# RMP_MAIN_HFB.net
KiCad netlist of a schematic drawn in Altium Designer
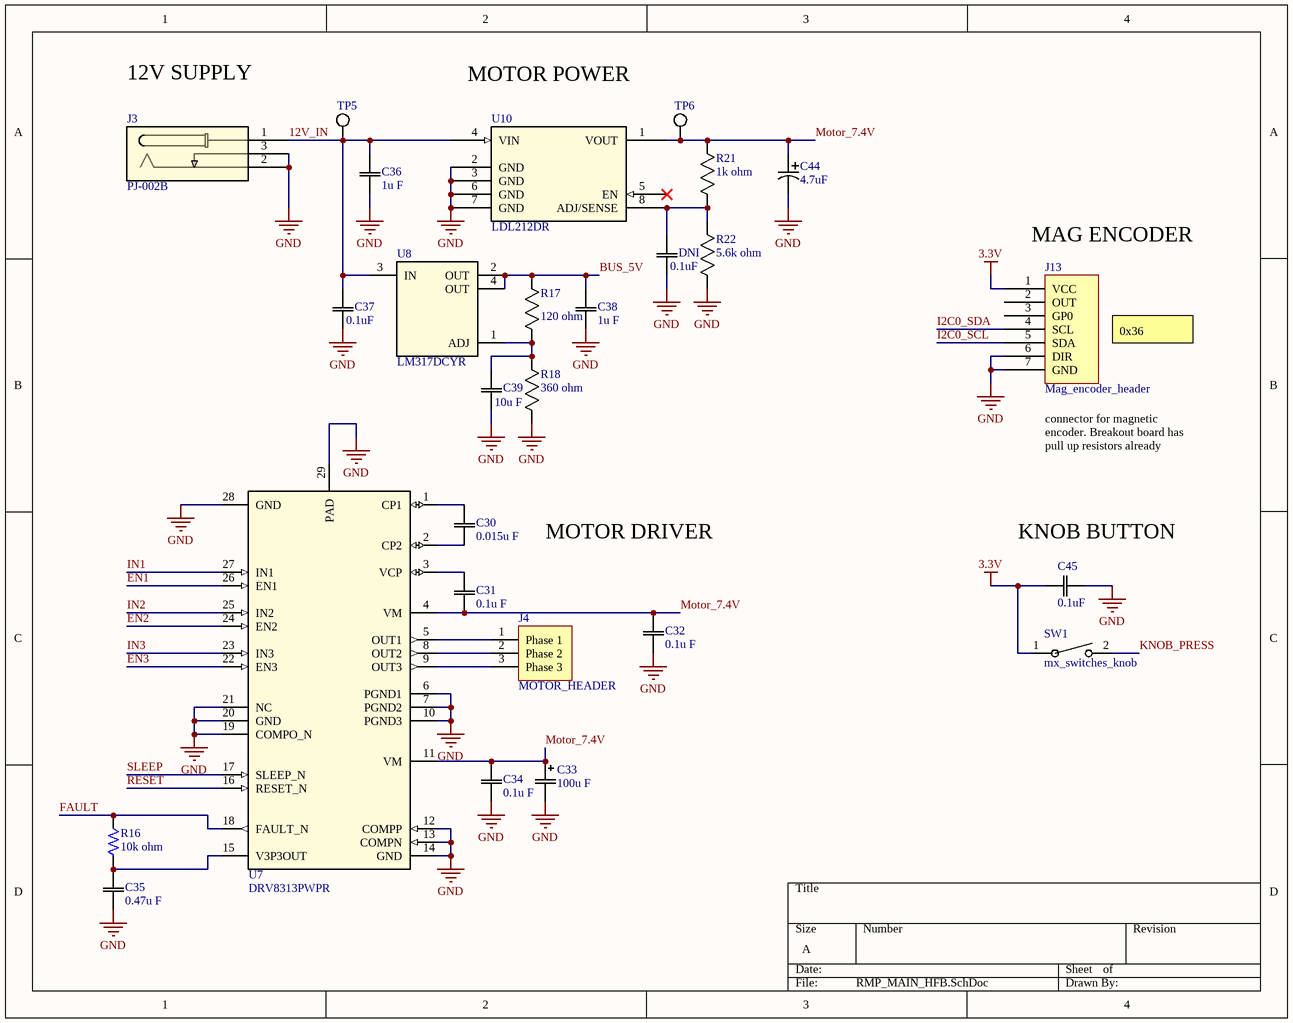
[diagram p0: RMP_MAIN_HFB.SchDoc]

(export (version "E")
  (design (tool "Eeschema 10.0.6"))
  (components
    (comp (ref "C30")
      (value "0.015u F")
      (footprint "CC0805N_YAG-M")
      (description "0.015 µF ±10% 50V Ceramic Capacitor X7R 0805 (2012 Metric)")
      (fields (field (name "Comment") "CC0805KRX7R9BB153"))
      (libsource (lib "Schlib1") (part "CAP_CC0805KRX7R9BB153"))
    )
    (comp (ref "C31")
      (value "0.1u F")
      (footprint "CC0805N_YAG-M")
      (description "0.1 µF ±10% 50V Ceramic Capacitor X7R 0805 (2012 Metric)")
      (fields (field (name "Comment") "CC0805KRX7R9BB104"))
      (libsource (lib "Schlib1") (part "CAP_CC0805KRX7R9BB104"))
    )
    (comp (ref "C32")
      (value "0.1u F")
      (footprint "CC0805N_YAG-M")
      (description "0.1 µF ±10% 50V Ceramic Capacitor X7R 0805 (2012 Metric)")
      (fields (field (name "Comment") "CC0805KRX7R9BB104"))
      (libsource (lib "Schlib1") (part "CAP_CC0805KRX7R9BB104"))
    )
    (comp (ref "C33")
      (value "100u F")
      (footprint "CAP_YX_6P3X11_RUB")
      (description "CAP ALUM 100UF 20% 35V RADIAL TH")
      (fields (field (name "Comment") "35YXJ100M6.3X11"))
      (libsource (lib "Schlib1") (part "CAP_35YXJ100M6.3X11"))
    )
    (comp (ref "C34")
      (value "0.1u F")
      (footprint "CC0805N_YAG-M")
      (description "0.1 µF ±10% 50V Ceramic Capacitor X7R 0805 (2012 Metric)")
      (fields (field (name "Comment") "CC0805KRX7R9BB104"))
      (libsource (lib "Schlib1") (part "CAP_CC0805KRX7R9BB104"))
    )
    (comp (ref "C35")
      (value "0.47u F")
      (footprint "CC0805N_YAG-M")
      (description "0.47 µF ±10% 25V Ceramic Capacitor X7R 0805 (2012 Metric)")
      (fields (field (name "Comment") "CC0805KKX7R8BB474"))
      (libsource (lib "Schlib1") (part "CAP_CC0805KKX7R8BB474"))
    )
    (comp (ref "C36")
      (value "1u F")
      (footprint "CAP_CL21B105KAFNNNE_SAM-M")
      (description "1 µF ±10% 25V Ceramic Capacitor X7R 0805 (2012 Metric)")
      (fields (field (name "Comment") "CL21B105KAFNNNE"))
      (libsource (lib "Schlib1") (part "CAP_CL21B105KAFNNNE"))
    )
    (comp (ref "C37")
      (value "0.1uF")
      (footprint "CC0805N_YAG-M")
      (description "0.1 µF ±10% 50V Ceramic Capacitor X7R 0805 (2012 Metric)")
      (fields (field (name "Comment") "CC0805KRX7R9BB104"))
      (libsource (lib "Schlib1") (part "CAP_CC0805KRX7R9BB104"))
    )
    (comp (ref "C38")
      (value "1u F")
      (footprint "CAP_CL21B105KAFNNNE_SAM-M")
      (description "1 µF ±10% 25V Ceramic Capacitor X7R 0805 (2012 Metric)")
      (fields (field (name "Comment") "CL21B105KAFNNNE"))
      (libsource (lib "Schlib1") (part "CAP_CL21B105KAFNNNE"))
    )
    (comp (ref "C39")
      (value "10u F")
      (footprint "G-21_MUR-M")
      (description "10 µF ±10% 16V Ceramic Capacitor X5R 0805 (2012 Metric)")
      (fields (field (name "Comment") "GRM21BR61C106KE15K"))
      (libsource (lib "Schlib1") (part "CAP_GRM21BR61C106KE15K"))
    )
    (comp (ref "C44")
      (value "4.7uF")
      (footprint "TAJA_AVX-M")
      (description "4.7 µF Molded Tantalum Capacitors 16 V 1206 (3216 Metric) 4Ohm")
      (fields (field (name "Comment") "TAJA475K016RNJ"))
      (libsource (lib "Schlib1") (part "CAP_TAJA475K016RNJ"))
    )
    (comp (ref "C45")
      (value "0.1uF")
      (footprint "CC0805N_YAG-M")
      (description "0.1 µF ±10% 50V Ceramic Capacitor X7R 0805 (2012 Metric)")
      (fields (field (name "Comment") "CC0805KRX7R9BB104"))
      (libsource (lib "Schlib1") (part "CAP_CC0805KRX7R9BB104"))
    )
    (comp (ref "DNI")
      (value "0.1uF")
      (footprint "CC0805N_YAG-M")
      (description "0.1 µF ±10% 50V Ceramic Capacitor X7R 0805 (2012 Metric)")
      (fields (field (name "Comment") "CC0805KRX7R9BB104"))
      (libsource (lib "Schlib1") (part "CAP_CC0805KRX7R9BB104"))
    )
    (comp (ref "J3")
      (value "PJ-002B")
      (footprint "PJ-002B_CUI")
      (description "Power Barrel Connector Jack 2.50mm ID (0.098\"), 5.50mm OD (0.217\") Through Hole, Right Angle")
      (libsource (lib "Schlib1") (part "PJ-002B"))
    )
    (comp (ref "J4")
      (value "MOTOR_HEADER")
      (footprint "3PINHEADER")
      (description "BLDC motor header")
      (libsource (lib "Schlib1") (part "MOTOR_HEADER"))
    )
    (comp (ref "J13")
      (value "Mag_encoder_header")
      (footprint "8PinHeader")
      (libsource (lib "Schlib1") (part "Mag_encoder_header"))
    )
    (comp (ref "R16")
      (value "10k ohm")
      (footprint "STA_RNCP0805_STP-M")
      (description "10 kOhms ±1% 0.25W, 1/4W Chip Resistor 0805 (2012 Metric) Anti-Sulfur Thin Film")
      (fields (field (name "Comment") "RNCP0805FTD10K0"))
      (libsource (lib "Schlib1") (part "RES_RNCP0805FTD10K0"))
    )
    (comp (ref "R17")
      (value "120 ohm")
      (footprint "RES_RNCF0805_STP-M")
      (description "120 Ohms ±0.5% 0.25W, 1/4W Chip Resistor 0805 (2012 Metric) Automotive AEC-Q200 Thin Film")
      (fields (field (name "Comment") "RNCF0805DTE120R"))
      (libsource (lib "Schlib1") (part "RES_RNCF0805DTE120R"))
    )
    (comp (ref "R18")
      (value "360 ohm")
      (footprint "RES_RNCF0805_STP-M")
      (description "360 Ohms ±0.5% 0.25W, 1/4W Chip Resistor 0805 (2012 Metric) Automotive AEC-Q200 Thin Film")
      (fields (field (name "Comment") "RNCF0805DTE360R"))
      (libsource (lib "Schlib1") (part "RES_RNCF0805DTE360R"))
    )
    (comp (ref "R21")
      (value "1k ohm")
      (footprint "RES_RNCF0805_STP-M")
      (description "1 kOhms ±0.5% 0.25W, 1/4W Chip Resistor 0805 (2012 Metric) Automotive AEC-Q200 Thin Film")
      (fields (field (name "Comment") "RNCF0805DTE1K00"))
      (libsource (lib "Schlib1") (part "RES_RNCF0805DTE1K00"))
    )
    (comp (ref "R22")
      (value "5.6k ohm")
      (footprint "RES_RNCF0805_STP-M")
      (description "5.6 kOhms ±0.5% 0.25W, 1/4W Chip Resistor 0805 (2012 Metric) Automotive AEC-Q200 Thin Film")
      (fields (field (name "Comment") "RNCF0805DTE5K60"))
      (libsource (lib "Schlib1") (part "RES_RNCF0805DTE5K60"))
    )
    (comp (ref "SW1")
      (value "mx_switches_knob")
      (footprint "knob_switches")
      (description "No Description Available")
      (libsource (lib "Schlib1") (part "mx_switches_knob"))
    )
    (comp (ref "TP5")
      (value "TestPoint")
      (footprint "Testpoint")
      (libsource (lib "Schlib1") (part "TestPoint"))
    )
    (comp (ref "TP6")
      (value "TestPoint")
      (footprint "Testpoint")
      (libsource (lib "Schlib1") (part "TestPoint"))
    )
    (comp (ref "U7")
      (value "DRV8313PWPR")
      (footprint "PWP0028F_M")
      (description "IC MOTOR DRIVER 8V-60V 28HTSSOP")
      (libsource (lib "Schlib1") (part "DRV8313PWPR"))
    )
    (comp (ref "U8")
      (value "LM317DCYR")
      (footprint "DCY0004A_M")
      (description "Linear Voltage Regulator IC Positive Adjustable 1 Output 1.5A SOT-223-4")
      (fields
        (field (name "ALTERNATE_PARTNUMBER") "LM317DCY")
        (field (name "MANUFACTURER") "Texas Instruments")
        (field (name "SYMBOLCREATER") "Altium")
      )
      (libsource (lib "Schlib1") (part "LM317DCYR"))
    )
    (comp (ref "U10")
      (value "LDL212DR")
      (footprint "SO8B_4X5X1P27_STM")
      (description "Linear Voltage Regulator IC Positive Adjustable 1 Output 1.2A 8-SO")
      (libsource (lib "Schlib1") (part "LDL212DR"))
    )
  )
  (nets
    (net (code "1") (name "/12V_IN") (class "Default")
      (node (ref "C36") (pin "2") (pinfunction "2_2") (pintype "passive"))
      (node (ref "C37") (pin "2") (pinfunction "2_2") (pintype "passive"))
      (node (ref "J3") (pin "1") (pinfunction "1_1") (pintype "passive"))
      (node (ref "TP5") (pin "1") (pinfunction "1_1") (pintype "passive"))
      (node (ref "U10") (pin "4") (pinfunction "VIN_4") (pintype "input"))
      (node (ref "U8") (pin "3") (pinfunction "IN_3") (pintype "power_in"))
    )
    (net (code "2") (name "/BUS_5V") (class "Default")
      (node (ref "C38") (pin "2") (pinfunction "2_2") (pintype "passive"))
      (node (ref "R17") (pin "2") (pinfunction "2_2") (pintype "passive"))
      (node (ref "U8") (pin "2") (pinfunction "OUT_2") (pintype "power_in"))
      (node (ref "U8") (pin "4") (pinfunction "OUT_4") (pintype "power_in"))
    )
    (net (code "3") (name "/EN1") (class "Default")
      (node (ref "U7") (pin "26") (pinfunction "EN1_26") (pintype "input"))
    )
    (net (code "4") (name "/EN2") (class "Default")
      (node (ref "U7") (pin "24") (pinfunction "EN2_24") (pintype "input"))
    )
    (net (code "5") (name "/EN3") (class "Default")
      (node (ref "U7") (pin "22") (pinfunction "EN3_22") (pintype "input"))
    )
    (net (code "6") (name "/FAULT") (class "Default")
      (node (ref "R16") (pin "2") (pinfunction "2_2") (pintype "passive"))
      (node (ref "U7") (pin "18") (pinfunction "FAULT_N_18") (pintype "output"))
    )
    (net (code "7") (name "/I2C0_SCL") (class "Default")
      (node (ref "J13") (pin "5") (pinfunction "SDA_5") (pintype "passive"))
    )
    (net (code "8") (name "/I2C0_SDA") (class "Default")
      (node (ref "J13") (pin "4") (pinfunction "SCL_4") (pintype "passive"))
    )
    (net (code "9") (name "/IN1") (class "Default")
      (node (ref "U7") (pin "27") (pinfunction "IN1_27") (pintype "input"))
    )
    (net (code "10") (name "/IN2") (class "Default")
      (node (ref "U7") (pin "25") (pinfunction "IN2_25") (pintype "input"))
    )
    (net (code "11") (name "/IN3") (class "Default")
      (node (ref "U7") (pin "23") (pinfunction "IN3_23") (pintype "input"))
    )
    (net (code "12") (name "/KNOB_PRESS") (class "Default")
      (node (ref "SW1") (pin "2") (pinfunction "2_2") (pintype "passive"))
    )
    (net (code "13") (name "/Motor_7.4V") (class "Default")
      (node (ref "C31") (pin "1") (pinfunction "1_1") (pintype "passive"))
      (node (ref "C32") (pin "2") (pinfunction "2_2") (pintype "passive"))
      (node (ref "C33") (pin "1") (pinfunction "1_1") (pintype "passive"))
      (node (ref "C34") (pin "2") (pinfunction "2_2") (pintype "passive"))
      (node (ref "C44") (pin "1") (pinfunction "1_1") (pintype "passive"))
      (node (ref "R21") (pin "2") (pinfunction "2_2") (pintype "passive"))
      (node (ref "TP6") (pin "1") (pinfunction "1_1") (pintype "passive"))
      (node (ref "U10") (pin "1") (pinfunction "VOUT_1") (pintype "power_in"))
      (node (ref "U7") (pin "11") (pinfunction "VM_11") (pintype "power_in"))
      (node (ref "U7") (pin "4") (pinfunction "VM_4") (pintype "power_in"))
    )
    (net (code "14") (name "/RESET") (class "Default")
      (node (ref "U7") (pin "16") (pinfunction "RESET_N_16") (pintype "input"))
    )
    (net (code "15") (name "/SLEEP") (class "Default")
      (node (ref "U7") (pin "17") (pinfunction "SLEEP_N_17") (pintype "input"))
    )
    (net (code "16") (name "3.3V") (class "Default")
      (node (ref "C45") (pin "2") (pinfunction "2_2") (pintype "passive"))
      (node (ref "J13") (pin "1") (pinfunction "VCC_1") (pintype "passive"))
      (node (ref "SW1") (pin "1") (pinfunction "1_1") (pintype "passive"))
    )
    (net (code "17") (name "GND") (class "Default")
      (node (ref "C32") (pin "1") (pinfunction "1_1") (pintype "passive"))
      (node (ref "C33") (pin "2") (pinfunction "2_2") (pintype "passive"))
      (node (ref "C34") (pin "1") (pinfunction "1_1") (pintype "passive"))
      (node (ref "C35") (pin "1") (pinfunction "1_1") (pintype "passive"))
      (node (ref "C36") (pin "1") (pinfunction "1_1") (pintype "passive"))
      (node (ref "C37") (pin "1") (pinfunction "1_1") (pintype "passive"))
      (node (ref "C38") (pin "1") (pinfunction "1_1") (pintype "passive"))
      (node (ref "C39") (pin "1") (pinfunction "1_1") (pintype "passive"))
      (node (ref "C44") (pin "2") (pinfunction "2_2") (pintype "passive"))
      (node (ref "C45") (pin "1") (pinfunction "1_1") (pintype "passive"))
      (node (ref "DNI") (pin "1") (pinfunction "1_1") (pintype "passive"))
      (node (ref "J13") (pin "6") (pinfunction "DIR_6") (pintype "passive"))
      (node (ref "J13") (pin "7") (pinfunction "GND_7") (pintype "passive"))
      (node (ref "J3") (pin "2") (pinfunction "2_2") (pintype "passive"))
      (node (ref "J3") (pin "3") (pinfunction "3_3") (pintype "passive"))
      (node (ref "R18") (pin "1") (pinfunction "1_1") (pintype "passive"))
      (node (ref "R22") (pin "1") (pinfunction "1_1") (pintype "passive"))
      (node (ref "U10") (pin "2") (pinfunction "GND_2") (pintype "power_in"))
      (node (ref "U10") (pin "3") (pinfunction "GND_3") (pintype "power_in"))
      (node (ref "U10") (pin "6") (pinfunction "GND_6") (pintype "power_in"))
      (node (ref "U10") (pin "7") (pinfunction "GND_7") (pintype "power_in"))
      (node (ref "U7") (pin "10") (pinfunction "PGND3_10") (pintype "power_in"))
      (node (ref "U7") (pin "12") (pinfunction "COMPP_12") (pintype "input"))
      (node (ref "U7") (pin "13") (pinfunction "COMPN_13") (pintype "input"))
      (node (ref "U7") (pin "14") (pinfunction "GND_14") (pintype "power_in"))
      (node (ref "U7") (pin "19") (pinfunction "COMPO_N_19") (pintype "power_in"))
      (node (ref "U7") (pin "20") (pinfunction "GND_20") (pintype "power_in"))
      (node (ref "U7") (pin "21") (pinfunction "NC_21") (pintype "passive"))
      (node (ref "U7") (pin "28") (pinfunction "GND_28") (pintype "power_in"))
      (node (ref "U7") (pin "29") (pinfunction "PAD_29") (pintype "power_in"))
      (node (ref "U7") (pin "6") (pinfunction "PGND1_6") (pintype "power_in"))
      (node (ref "U7") (pin "7") (pinfunction "PGND2_7") (pintype "power_in"))
    )
    (net (code "18") (name "Net-(J4-Phase_1)") (class "Default")
      (node (ref "J4") (pin "1") (pinfunction "Phase_1_1") (pintype "passive"))
      (node (ref "U7") (pin "5") (pinfunction "OUT1_5") (pintype "output"))
    )
    (net (code "19") (name "Net-(J4-Phase_2)") (class "Default")
      (node (ref "J4") (pin "2") (pinfunction "Phase_2_2") (pintype "passive"))
      (node (ref "U7") (pin "8") (pinfunction "OUT2_8") (pintype "output"))
    )
    (net (code "20") (name "Net-(J4-Phase_3)") (class "Default")
      (node (ref "J4") (pin "3") (pinfunction "Phase_3_3") (pintype "passive"))
      (node (ref "U7") (pin "9") (pinfunction "OUT3_9") (pintype "output"))
    )
    (net (code "21") (name "Net-(U7-CP1)") (class "Default")
      (node (ref "C30") (pin "2") (pinfunction "2_2") (pintype "passive"))
      (node (ref "U7") (pin "1") (pinfunction "CP1_1") (pintype "bidirectional"))
    )
    (net (code "22") (name "Net-(U7-CP2)") (class "Default")
      (node (ref "C30") (pin "1") (pinfunction "1_1") (pintype "passive"))
      (node (ref "U7") (pin "2") (pinfunction "CP2_2") (pintype "bidirectional"))
    )
    (net (code "23") (name "Net-(U7-V3P3OUT)") (class "Default")
      (node (ref "C35") (pin "2") (pinfunction "2_2") (pintype "passive"))
      (node (ref "R16") (pin "1") (pinfunction "1_1") (pintype "passive"))
      (node (ref "U7") (pin "15") (pinfunction "V3P3OUT_15") (pintype "power_in"))
    )
    (net (code "24") (name "Net-(U7-VCP)") (class "Default")
      (node (ref "C31") (pin "2") (pinfunction "2_2") (pintype "passive"))
      (node (ref "U7") (pin "3") (pinfunction "VCP_3") (pintype "bidirectional"))
    )
    (net (code "25") (name "Net-(U8-ADJ)") (class "Default")
      (node (ref "C39") (pin "2") (pinfunction "2_2") (pintype "passive"))
      (node (ref "R17") (pin "1") (pinfunction "1_1") (pintype "passive"))
      (node (ref "R18") (pin "2") (pinfunction "2_2") (pintype "passive"))
      (node (ref "U8") (pin "1") (pinfunction "ADJ_1") (pintype "power_in"))
    )
    (net (code "26") (name "Net-(U10-ADJ{slash}SENSE)") (class "Default")
      (node (ref "DNI") (pin "2") (pinfunction "2_2") (pintype "passive"))
      (node (ref "R21") (pin "1") (pinfunction "1_1") (pintype "passive"))
      (node (ref "R22") (pin "2") (pinfunction "2_2") (pintype "passive"))
      (node (ref "U10") (pin "8") (pinfunction "ADJ/SENSE_8") (pintype "passive"))
    )
    (net (code "27") (name "unconnected-(J13-GP0-Pad3)") (class "Default")
      (node (ref "J13") (pin "3") (pinfunction "GP0_3") (pintype "passive"))
    )
    (net (code "28") (name "unconnected-(J13-OUT-Pad2)") (class "Default")
      (node (ref "J13") (pin "2") (pinfunction "OUT_2") (pintype "passive"))
    )
    (net (code "29") (name "unconnected-(U10-EN-Pad5)") (class "Default")
      (node (ref "U10") (pin "5") (pinfunction "EN_5") (pintype "input+no_connect"))
    )
  )
)
